# STM32F446RC_single_layer_V2.net
KiCad netlist of a schematic drawn in EAGLE
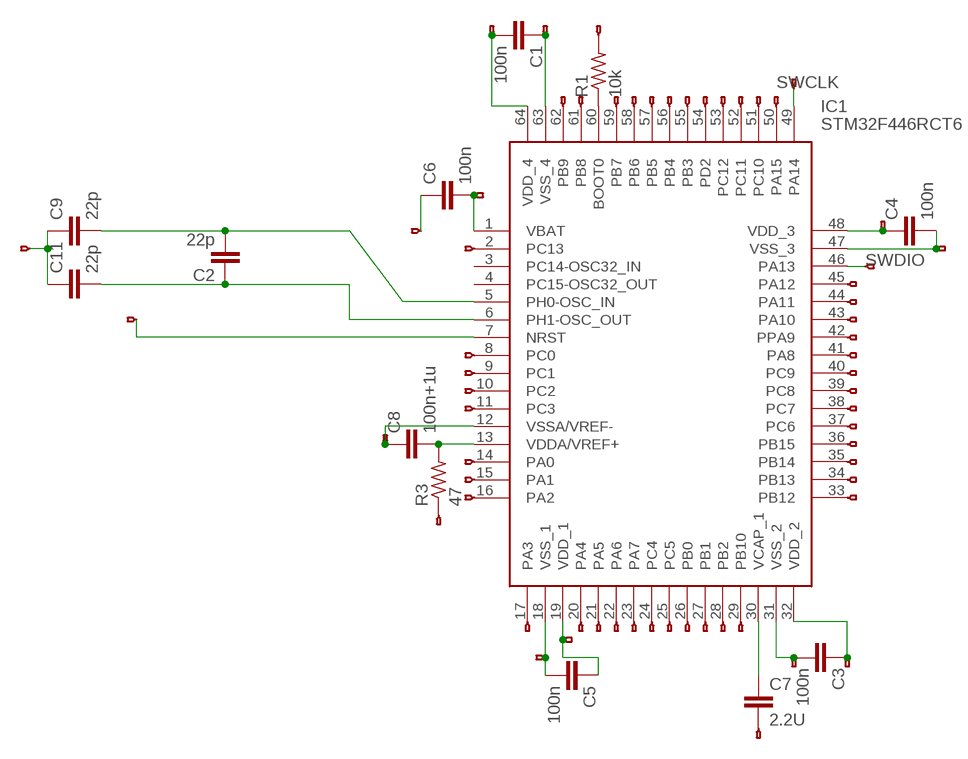
[diagram p0: schematic, sheet 1]

(export (version "E")
  (design (tool "Eeschema 10.0.6"))
  (components
    (comp (ref "C1")
      (value "100n")
      (footprint "eagle-import:C2.5-3")
      (libsource (lib "eagle-import") (part "C2,5-3"))
    )
    (comp (ref "C2")
      (value "22p")
      (footprint "eagle-import:C2.5-3")
      (libsource (lib "eagle-import") (part "C2,5-3"))
    )
    (comp (ref "C3")
      (value "100n")
      (footprint "eagle-import:C2.5-3")
      (libsource (lib "eagle-import") (part "C2,5-3"))
    )
    (comp (ref "C4")
      (value "100n")
      (footprint "eagle-import:C2.5-3")
      (libsource (lib "eagle-import") (part "C2,5-3"))
    )
    (comp (ref "C5")
      (value "100n")
      (footprint "eagle-import:C2.5-3")
      (libsource (lib "eagle-import") (part "C2,5-3"))
    )
    (comp (ref "C6")
      (value "100n")
      (footprint "eagle-import:C2.5-3")
      (libsource (lib "eagle-import") (part "C2,5-3"))
    )
    (comp (ref "C7")
      (value "2.2U")
      (footprint "eagle-import:C2.5-3")
      (libsource (lib "eagle-import") (part "C2,5-3"))
    )
    (comp (ref "C8")
      (value "100n+1u")
      (footprint "eagle-import:C2.5-3")
      (libsource (lib "eagle-import") (part "C2,5-3"))
    )
    (comp (ref "C9")
      (value "22p")
      (footprint "eagle-import:C2.5-3")
      (libsource (lib "eagle-import") (part "C2,5-3"))
    )
    (comp (ref "C11")
      (value "22p")
      (footprint "eagle-import:C2.5-3")
      (libsource (lib "eagle-import") (part "C2,5-3"))
    )
    (comp (ref "IC1")
      (value "STM32F446RCT6")
      (footprint "eagle-import:QFP50P1200X1200X160-64N")
      (fields (field (name "MOUSER_PART_NUMBER") "511-STM32F446RCT6"))
      (libsource (lib "eagle-import") (part "STM32F446RCT6"))
    )
    (comp (ref "JP1")
      (value "HEADERHOLE-HEADERHOLE")
      (footprint "eagle-import:1X1-HEADER-HOLE")
      (libsource (lib "eagle-import") (part "HEADERHOLE-HEADERHOLE"))
    )
    (comp (ref "JP2")
      (value "HEADERHOLE-HEADERHOLE")
      (footprint "eagle-import:1X1-HEADER-HOLE")
      (libsource (lib "eagle-import") (part "HEADERHOLE-HEADERHOLE"))
    )
    (comp (ref "JP3")
      (value "HEADERHOLE-HEADERHOLE")
      (footprint "eagle-import:1X1-HEADER-HOLE")
      (libsource (lib "eagle-import") (part "HEADERHOLE-HEADERHOLE"))
    )
    (comp (ref "JP4")
      (value "HEADERHOLE-HEADERHOLE")
      (footprint "eagle-import:1X1-HEADER-HOLE")
      (libsource (lib "eagle-import") (part "HEADERHOLE-HEADERHOLE"))
    )
    (comp (ref "JP5")
      (value "HEADERHOLE-HEADERHOLE")
      (footprint "eagle-import:1X1-HEADER-HOLE")
      (libsource (lib "eagle-import") (part "HEADERHOLE-HEADERHOLE"))
    )
    (comp (ref "JP6")
      (value "HEADERHOLE-HEADERHOLE")
      (footprint "eagle-import:1X1-HEADER-HOLE")
      (libsource (lib "eagle-import") (part "HEADERHOLE-HEADERHOLE"))
    )
    (comp (ref "JP7")
      (value "HEADERHOLE-HEADERHOLE")
      (footprint "eagle-import:1X1-HEADER-HOLE")
      (libsource (lib "eagle-import") (part "HEADERHOLE-HEADERHOLE"))
    )
    (comp (ref "JP9")
      (value "HEADERHOLE-HEADERHOLE")
      (footprint "eagle-import:1X1-HEADER-HOLE")
      (libsource (lib "eagle-import") (part "HEADERHOLE-HEADERHOLE"))
    )
    (comp (ref "JP10")
      (value "HEADERHOLE-HEADERHOLE")
      (footprint "eagle-import:1X1-HEADER-HOLE")
      (libsource (lib "eagle-import") (part "HEADERHOLE-HEADERHOLE"))
    )
    (comp (ref "JP11")
      (value "HEADERHOLE-HEADERHOLE")
      (footprint "eagle-import:1X1-HEADER-HOLE")
      (libsource (lib "eagle-import") (part "HEADERHOLE-HEADERHOLE"))
    )
    (comp (ref "JP12")
      (value "HEADERHOLE-HEADERHOLE")
      (footprint "eagle-import:1X1-HEADER-HOLE")
      (libsource (lib "eagle-import") (part "HEADERHOLE-HEADERHOLE"))
    )
    (comp (ref "JP13")
      (value "HEADERHOLE-HEADERHOLE")
      (footprint "eagle-import:1X1-HEADER-HOLE")
      (libsource (lib "eagle-import") (part "HEADERHOLE-HEADERHOLE"))
    )
    (comp (ref "JP14")
      (value "HEADERHOLE-HEADERHOLE")
      (footprint "eagle-import:1X1-HEADER-HOLE")
      (libsource (lib "eagle-import") (part "HEADERHOLE-HEADERHOLE"))
    )
    (comp (ref "JP15")
      (value "HEADERHOLE-HEADERHOLE")
      (footprint "eagle-import:1X1-HEADER-HOLE")
      (libsource (lib "eagle-import") (part "HEADERHOLE-HEADERHOLE"))
    )
    (comp (ref "JP16")
      (value "HEADERHOLE-HEADERHOLE")
      (footprint "eagle-import:1X1-HEADER-HOLE")
      (libsource (lib "eagle-import") (part "HEADERHOLE-HEADERHOLE"))
    )
    (comp (ref "JP17")
      (value "HEADERHOLE-HEADERHOLE")
      (footprint "eagle-import:1X1-HEADER-HOLE")
      (libsource (lib "eagle-import") (part "HEADERHOLE-HEADERHOLE"))
    )
    (comp (ref "JP18")
      (value "HEADERHOLE-HEADERHOLE")
      (footprint "eagle-import:1X1-HEADER-HOLE")
      (libsource (lib "eagle-import") (part "HEADERHOLE-HEADERHOLE"))
    )
    (comp (ref "JP19")
      (value "HEADERHOLE-HEADERHOLE")
      (footprint "eagle-import:1X1-HEADER-HOLE")
      (libsource (lib "eagle-import") (part "HEADERHOLE-HEADERHOLE"))
    )
    (comp (ref "JP20")
      (value "HEADERHOLE-HEADERHOLE")
      (footprint "eagle-import:1X1-HEADER-HOLE")
      (libsource (lib "eagle-import") (part "HEADERHOLE-HEADERHOLE"))
    )
    (comp (ref "JP21")
      (value "HEADERHOLE-HEADERHOLE")
      (footprint "eagle-import:1X1-HEADER-HOLE")
      (libsource (lib "eagle-import") (part "HEADERHOLE-HEADERHOLE"))
    )
    (comp (ref "JP22")
      (value "HEADERHOLE-HEADERHOLE")
      (footprint "eagle-import:1X1-HEADER-HOLE")
      (libsource (lib "eagle-import") (part "HEADERHOLE-HEADERHOLE"))
    )
    (comp (ref "JP23")
      (value "HEADERHOLE-HEADERHOLE")
      (footprint "eagle-import:1X1-HEADER-HOLE")
      (libsource (lib "eagle-import") (part "HEADERHOLE-HEADERHOLE"))
    )
    (comp (ref "JP24")
      (value "HEADERHOLE-HEADERHOLE")
      (footprint "eagle-import:1X1-HEADER-HOLE")
      (libsource (lib "eagle-import") (part "HEADERHOLE-HEADERHOLE"))
    )
    (comp (ref "JP25")
      (value "HEADERHOLE-HEADERHOLE")
      (footprint "eagle-import:1X1-HEADER-HOLE")
      (libsource (lib "eagle-import") (part "HEADERHOLE-HEADERHOLE"))
    )
    (comp (ref "JP26")
      (value "HEADERHOLE-HEADERHOLE")
      (footprint "eagle-import:1X1-HEADER-HOLE")
      (libsource (lib "eagle-import") (part "HEADERHOLE-HEADERHOLE"))
    )
    (comp (ref "JP27")
      (value "HEADERHOLE-HEADERHOLE")
      (footprint "eagle-import:1X1-HEADER-HOLE")
      (libsource (lib "eagle-import") (part "HEADERHOLE-HEADERHOLE"))
    )
    (comp (ref "JP28")
      (value "HEADERHOLE-HEADERHOLE")
      (footprint "eagle-import:1X1-HEADER-HOLE")
      (libsource (lib "eagle-import") (part "HEADERHOLE-HEADERHOLE"))
    )
    (comp (ref "JP29")
      (value "HEADERHOLE-HEADERHOLE")
      (footprint "eagle-import:1X1-HEADER-HOLE")
      (libsource (lib "eagle-import") (part "HEADERHOLE-HEADERHOLE"))
    )
    (comp (ref "JP30")
      (value "HEADERHOLE-HEADERHOLE")
      (footprint "eagle-import:1X1-HEADER-HOLE")
      (libsource (lib "eagle-import") (part "HEADERHOLE-HEADERHOLE"))
    )
    (comp (ref "JP31")
      (value "HEADERHOLE-HEADERHOLE")
      (footprint "eagle-import:1X1-HEADER-HOLE")
      (libsource (lib "eagle-import") (part "HEADERHOLE-HEADERHOLE"))
    )
    (comp (ref "JP32")
      (value "HEADERHOLE-HEADERHOLE")
      (footprint "eagle-import:1X1-HEADER-HOLE")
      (libsource (lib "eagle-import") (part "HEADERHOLE-HEADERHOLE"))
    )
    (comp (ref "JP33")
      (value "HEADERHOLE-HEADERHOLE")
      (footprint "eagle-import:1X1-HEADER-HOLE")
      (libsource (lib "eagle-import") (part "HEADERHOLE-HEADERHOLE"))
    )
    (comp (ref "JP34")
      (value "HEADERHOLE-HEADERHOLE")
      (footprint "eagle-import:1X1-HEADER-HOLE")
      (libsource (lib "eagle-import") (part "HEADERHOLE-HEADERHOLE"))
    )
    (comp (ref "JP35")
      (value "HEADERHOLE-HEADERHOLE")
      (footprint "eagle-import:1X1-HEADER-HOLE")
      (libsource (lib "eagle-import") (part "HEADERHOLE-HEADERHOLE"))
    )
    (comp (ref "JP36")
      (value "HEADERHOLE-HEADERHOLE")
      (footprint "eagle-import:1X1-HEADER-HOLE")
      (libsource (lib "eagle-import") (part "HEADERHOLE-HEADERHOLE"))
    )
    (comp (ref "JP37")
      (value "HEADERHOLE-HEADERHOLE")
      (footprint "eagle-import:1X1-HEADER-HOLE")
      (libsource (lib "eagle-import") (part "HEADERHOLE-HEADERHOLE"))
    )
    (comp (ref "JP38")
      (value "HEADERHOLE-HEADERHOLE")
      (footprint "eagle-import:1X1-HEADER-HOLE")
      (libsource (lib "eagle-import") (part "HEADERHOLE-HEADERHOLE"))
    )
    (comp (ref "JP39")
      (value "HEADERHOLE-HEADERHOLE")
      (footprint "eagle-import:1X1-HEADER-HOLE")
      (libsource (lib "eagle-import") (part "HEADERHOLE-HEADERHOLE"))
    )
    (comp (ref "JP40")
      (value "HEADERHOLE-HEADERHOLE")
      (footprint "eagle-import:1X1-HEADER-HOLE")
      (libsource (lib "eagle-import") (part "HEADERHOLE-HEADERHOLE"))
    )
    (comp (ref "JP41")
      (value "HEADERHOLE-HEADERHOLE")
      (footprint "eagle-import:1X1-HEADER-HOLE")
      (libsource (lib "eagle-import") (part "HEADERHOLE-HEADERHOLE"))
    )
    (comp (ref "JP42")
      (value "HEADERHOLE-HEADERHOLE")
      (footprint "eagle-import:1X1-HEADER-HOLE")
      (libsource (lib "eagle-import") (part "HEADERHOLE-HEADERHOLE"))
    )
    (comp (ref "JP43")
      (value "HEADERHOLE-HEADERHOLE")
      (footprint "eagle-import:1X1-HEADER-HOLE")
      (libsource (lib "eagle-import") (part "HEADERHOLE-HEADERHOLE"))
    )
    (comp (ref "JP44")
      (value "HEADERHOLE-HEADERHOLE")
      (footprint "eagle-import:1X1-HEADER-HOLE")
      (libsource (lib "eagle-import") (part "HEADERHOLE-HEADERHOLE"))
    )
    (comp (ref "JP45")
      (value "HEADERHOLE-HEADERHOLE")
      (footprint "eagle-import:1X1-HEADER-HOLE")
      (libsource (lib "eagle-import") (part "HEADERHOLE-HEADERHOLE"))
    )
    (comp (ref "JP46")
      (value "HEADERHOLE-HEADERHOLE")
      (footprint "eagle-import:1X1-HEADER-HOLE")
      (libsource (lib "eagle-import") (part "HEADERHOLE-HEADERHOLE"))
    )
    (comp (ref "JP47")
      (value "HEADERHOLE-HEADERHOLE")
      (footprint "eagle-import:1X1-HEADER-HOLE")
      (libsource (lib "eagle-import") (part "HEADERHOLE-HEADERHOLE"))
    )
    (comp (ref "JP48")
      (value "HEADERHOLE-HEADERHOLE")
      (footprint "eagle-import:1X1-HEADER-HOLE")
      (libsource (lib "eagle-import") (part "HEADERHOLE-HEADERHOLE"))
    )
    (comp (ref "JP49")
      (value "HEADERHOLE-HEADERHOLE")
      (footprint "eagle-import:1X1-HEADER-HOLE")
      (libsource (lib "eagle-import") (part "HEADERHOLE-HEADERHOLE"))
    )
    (comp (ref "JP50")
      (value "HEADERHOLE-HEADERHOLE")
      (footprint "eagle-import:1X1-HEADER-HOLE")
      (libsource (lib "eagle-import") (part "HEADERHOLE-HEADERHOLE"))
    )
    (comp (ref "JP51")
      (value "HEADERHOLE-HEADERHOLE")
      (footprint "eagle-import:1X1-HEADER-HOLE")
      (libsource (lib "eagle-import") (part "HEADERHOLE-HEADERHOLE"))
    )
    (comp (ref "JP52")
      (value "HEADERHOLE-HEADERHOLE")
      (footprint "eagle-import:1X1-HEADER-HOLE")
      (libsource (lib "eagle-import") (part "HEADERHOLE-HEADERHOLE"))
    )
    (comp (ref "JP53")
      (value "HEADERHOLE-HEADERHOLE")
      (footprint "eagle-import:1X1-HEADER-HOLE")
      (libsource (lib "eagle-import") (part "HEADERHOLE-HEADERHOLE"))
    )
    (comp (ref "JP54")
      (value "HEADERHOLE-HEADERHOLE")
      (footprint "eagle-import:1X1-HEADER-HOLE")
      (libsource (lib "eagle-import") (part "HEADERHOLE-HEADERHOLE"))
    )
    (comp (ref "JP55")
      (value "HEADERHOLE-HEADERHOLE")
      (footprint "eagle-import:1X1-HEADER-HOLE")
      (libsource (lib "eagle-import") (part "HEADERHOLE-HEADERHOLE"))
    )
    (comp (ref "JP56")
      (value "HEADERHOLE-HEADERHOLE")
      (footprint "eagle-import:1X1-HEADER-HOLE")
      (libsource (lib "eagle-import") (part "HEADERHOLE-HEADERHOLE"))
    )
    (comp (ref "JP57")
      (value "HEADERHOLE-HEADERHOLE")
      (footprint "eagle-import:1X1-HEADER-HOLE")
      (libsource (lib "eagle-import") (part "HEADERHOLE-HEADERHOLE"))
    )
    (comp (ref "JP58")
      (value "HEADERHOLE-HEADERHOLE")
      (footprint "eagle-import:1X1-HEADER-HOLE")
      (libsource (lib "eagle-import") (part "HEADERHOLE-HEADERHOLE"))
    )
    (comp (ref "JP59")
      (value "HEADERHOLE-HEADERHOLE")
      (footprint "eagle-import:1X1-HEADER-HOLE")
      (libsource (lib "eagle-import") (part "HEADERHOLE-HEADERHOLE"))
    )
    (comp (ref "JP61")
      (value "HEADERHOLE-HEADERHOLE")
      (footprint "eagle-import:1X1-HEADER-HOLE")
      (libsource (lib "eagle-import") (part "HEADERHOLE-HEADERHOLE"))
    )
    (comp (ref "JP62")
      (value "HEADERHOLE-HEADERHOLE")
      (footprint "eagle-import:1X1-HEADER-HOLE")
      (libsource (lib "eagle-import") (part "HEADERHOLE-HEADERHOLE"))
    )
    (comp (ref "JP63")
      (value "HEADERHOLE-HEADERHOLE")
      (footprint "eagle-import:1X1-HEADER-HOLE")
      (libsource (lib "eagle-import") (part "HEADERHOLE-HEADERHOLE"))
    )
    (comp (ref "JP65")
      (value "HEADERHOLE-HEADERHOLE")
      (footprint "eagle-import:1X1-HEADER-HOLE")
      (libsource (lib "eagle-import") (part "HEADERHOLE-HEADERHOLE"))
    )
    (comp (ref "R1")
      (value "10k")
      (footprint "eagle-import:0204V")
      (libsource (lib "eagle-import") (part "R-US_0204/2V"))
    )
    (comp (ref "R3")
      (value "47")
      (footprint "eagle-import:0204V")
      (libsource (lib "eagle-import") (part "R-US_0204/2V"))
    )
  )
  (nets
    (net (code "1") (name "/SWCLK") (class "Default")
      (node (ref "IC1") (pin "49") (pinfunction "PA14_49") (pintype "bidirectional"))
      (node (ref "JP55") (pin "1") (pinfunction "P$1_1") (pintype "bidirectional"))
    )
    (net (code "2") (name "/SWDIO") (class "Default")
      (node (ref "IC1") (pin "46") (pinfunction "PA13_46") (pintype "bidirectional"))
      (node (ref "JP54") (pin "1") (pinfunction "P$1_1") (pintype "bidirectional"))
    )
    (net (code "3") (name "Net-(IC1-BOOT0)") (class "Default")
      (node (ref "IC1") (pin "60") (pinfunction "BOOT0_60") (pintype "bidirectional"))
      (node (ref "R1") (pin "1") (pinfunction "1_1") (pintype "passive"))
    )
    (net (code "4") (name "Net-(IC1-NRST)") (class "Default")
      (node (ref "IC1") (pin "7") (pinfunction "NRST_7") (pintype "bidirectional"))
      (node (ref "JP63") (pin "1") (pinfunction "P$1_1") (pintype "bidirectional"))
    )
    (net (code "5") (name "Net-(IC1-PA0)") (class "Default")
      (node (ref "IC1") (pin "14") (pinfunction "PA0_14") (pintype "bidirectional"))
      (node (ref "JP34") (pin "1") (pinfunction "P$1_1") (pintype "bidirectional"))
    )
    (net (code "6") (name "Net-(IC1-PA1)") (class "Default")
      (node (ref "IC1") (pin "15") (pinfunction "PA1_15") (pintype "bidirectional"))
      (node (ref "JP35") (pin "1") (pinfunction "P$1_1") (pintype "bidirectional"))
    )
    (net (code "7") (name "Net-(IC1-PA2)") (class "Default")
      (node (ref "IC1") (pin "16") (pinfunction "PA2_16") (pintype "bidirectional"))
      (node (ref "JP36") (pin "1") (pinfunction "P$1_1") (pintype "bidirectional"))
    )
    (net (code "8") (name "Net-(IC1-PA3)") (class "Default")
      (node (ref "IC1") (pin "17") (pinfunction "PA3_17") (pintype "bidirectional"))
      (node (ref "JP24") (pin "1") (pinfunction "P$1_1") (pintype "bidirectional"))
    )
    (net (code "9") (name "Net-(IC1-PA4)") (class "Default")
      (node (ref "IC1") (pin "20") (pinfunction "PA4_20") (pintype "bidirectional"))
      (node (ref "JP21") (pin "1") (pinfunction "P$1_1") (pintype "bidirectional"))
    )
    (net (code "10") (name "Net-(IC1-PA5)") (class "Default")
      (node (ref "IC1") (pin "21") (pinfunction "PA5_21") (pintype "bidirectional"))
      (node (ref "JP19") (pin "1") (pinfunction "P$1_1") (pintype "bidirectional"))
    )
    (net (code "11") (name "Net-(IC1-PA6)") (class "Default")
      (node (ref "IC1") (pin "22") (pinfunction "PA6_22") (pintype "bidirectional"))
      (node (ref "JP9") (pin "1") (pinfunction "P$1_1") (pintype "bidirectional"))
    )
    (net (code "12") (name "Net-(IC1-PA7)") (class "Default")
      (node (ref "IC1") (pin "23") (pinfunction "PA7_23") (pintype "bidirectional"))
      (node (ref "JP11") (pin "1") (pinfunction "P$1_1") (pintype "bidirectional"))
    )
    (net (code "13") (name "Net-(IC1-PA8)") (class "Default")
      (node (ref "IC1") (pin "41") (pinfunction "PA8_41") (pintype "bidirectional"))
      (node (ref "JP28") (pin "1") (pinfunction "P$1_1") (pintype "bidirectional"))
    )
    (net (code "14") (name "Net-(IC1-PA10)") (class "Default")
      (node (ref "IC1") (pin "43") (pinfunction "PA10_43") (pintype "bidirectional"))
      (node (ref "JP33") (pin "1") (pinfunction "P$1_1") (pintype "bidirectional"))
    )
    (net (code "15") (name "Net-(IC1-PA11)") (class "Default")
      (node (ref "IC1") (pin "44") (pinfunction "PA11_44") (pintype "bidirectional"))
      (node (ref "JP32") (pin "1") (pinfunction "P$1_1") (pintype "bidirectional"))
    )
    (net (code "16") (name "Net-(IC1-PA12)") (class "Default")
      (node (ref "IC1") (pin "45") (pinfunction "PA12_45") (pintype "bidirectional"))
      (node (ref "JP25") (pin "1") (pinfunction "P$1_1") (pintype "bidirectional"))
    )
    (net (code "17") (name "Net-(IC1-PA15)") (class "Default")
      (node (ref "IC1") (pin "50") (pinfunction "PA15_50") (pintype "bidirectional"))
      (node (ref "JP45") (pin "1") (pinfunction "P$1_1") (pintype "bidirectional"))
    )
    (net (code "18") (name "Net-(IC1-PB0)") (class "Default")
      (node (ref "IC1") (pin "26") (pinfunction "PB0_26") (pintype "bidirectional"))
      (node (ref "JP22") (pin "1") (pinfunction "P$1_1") (pintype "bidirectional"))
    )
    (net (code "19") (name "Net-(IC1-PB1)") (class "Default")
      (node (ref "IC1") (pin "27") (pinfunction "PB1_27") (pintype "bidirectional"))
      (node (ref "JP17") (pin "1") (pinfunction "P$1_1") (pintype "bidirectional"))
    )
    (net (code "20") (name "Net-(IC1-PB2)") (class "Default")
      (node (ref "IC1") (pin "28") (pinfunction "PB2_28") (pintype "bidirectional"))
      (node (ref "JP16") (pin "1") (pinfunction "P$1_1") (pintype "bidirectional"))
    )
    (net (code "21") (name "Net-(IC1-PB3)") (class "Default")
      (node (ref "IC1") (pin "55") (pinfunction "PB3_55") (pintype "bidirectional"))
      (node (ref "JP44") (pin "1") (pinfunction "P$1_1") (pintype "bidirectional"))
    )
    (net (code "22") (name "Net-(IC1-PB4)") (class "Default")
      (node (ref "IC1") (pin "56") (pinfunction "PB4_56") (pintype "bidirectional"))
      (node (ref "JP40") (pin "1") (pinfunction "P$1_1") (pintype "bidirectional"))
    )
    (net (code "23") (name "Net-(IC1-PB5)") (class "Default")
      (node (ref "IC1") (pin "57") (pinfunction "PB5_57") (pintype "bidirectional"))
      (node (ref "JP41") (pin "1") (pinfunction "P$1_1") (pintype "bidirectional"))
    )
    (net (code "24") (name "Net-(IC1-PB6)") (class "Default")
      (node (ref "IC1") (pin "58") (pinfunction "PB6_58") (pintype "bidirectional"))
      (node (ref "JP42") (pin "1") (pinfunction "P$1_1") (pintype "bidirectional"))
    )
    (net (code "25") (name "Net-(IC1-PB7)") (class "Default")
      (node (ref "IC1") (pin "59") (pinfunction "PB7_59") (pintype "bidirectional"))
      (node (ref "JP43") (pin "1") (pinfunction "P$1_1") (pintype "bidirectional"))
    )
    (net (code "26") (name "Net-(IC1-PB8)") (class "Default")
      (node (ref "IC1") (pin "61") (pinfunction "PB8_61") (pintype "bidirectional"))
      (node (ref "JP46") (pin "1") (pinfunction "P$1_1") (pintype "bidirectional"))
    )
    (net (code "27") (name "Net-(IC1-PB9)") (class "Default")
      (node (ref "IC1") (pin "62") (pinfunction "PB9_62") (pintype "bidirectional"))
      (node (ref "JP47") (pin "1") (pinfunction "P$1_1") (pintype "bidirectional"))
    )
    (net (code "28") (name "Net-(IC1-PB10)") (class "Default")
      (node (ref "IC1") (pin "29") (pinfunction "PB10_29") (pintype "bidirectional"))
      (node (ref "JP14") (pin "1") (pinfunction "P$1_1") (pintype "bidirectional"))
    )
    (net (code "29") (name "Net-(IC1-PB12)") (class "Default")
      (node (ref "IC1") (pin "33") (pinfunction "PB12_33") (pintype "bidirectional"))
      (node (ref "JP18") (pin "1") (pinfunction "P$1_1") (pintype "bidirectional"))
    )
    (net (code "30") (name "Net-(IC1-PB13)") (class "Default")
      (node (ref "IC1") (pin "34") (pinfunction "PB13_34") (pintype "bidirectional"))
      (node (ref "JP13") (pin "1") (pinfunction "P$1_1") (pintype "bidirectional"))
    )
    (net (code "31") (name "Net-(IC1-PB14)") (class "Default")
      (node (ref "IC1") (pin "35") (pinfunction "PB14_35") (pintype "bidirectional"))
      (node (ref "JP6") (pin "1") (pinfunction "P$1_1") (pintype "bidirectional"))
    )
    (net (code "32") (name "Net-(IC1-PB15)") (class "Default")
      (node (ref "IC1") (pin "36") (pinfunction "PB15_36") (pintype "bidirectional"))
      (node (ref "JP10") (pin "1") (pinfunction "P$1_1") (pintype "bidirectional"))
    )
    (net (code "33") (name "Net-(IC1-PC0)") (class "Default")
      (node (ref "IC1") (pin "8") (pinfunction "PC0_8") (pintype "bidirectional"))
      (node (ref "JP29") (pin "1") (pinfunction "P$1_1") (pintype "bidirectional"))
    )
    (net (code "34") (name "Net-(IC1-PC1)") (class "Default")
      (node (ref "IC1") (pin "9") (pinfunction "PC1_9") (pintype "bidirectional"))
      (node (ref "JP27") (pin "1") (pinfunction "P$1_1") (pintype "bidirectional"))
    )
    (net (code "35") (name "Net-(IC1-PC2)") (class "Default")
      (node (ref "IC1") (pin "10") (pinfunction "PC2_10") (pintype "bidirectional"))
      (node (ref "JP3") (pin "1") (pinfunction "P$1_1") (pintype "bidirectional"))
    )
    (net (code "36") (name "Net-(IC1-PC3)") (class "Default")
      (node (ref "IC1") (pin "11") (pinfunction "PC3_11") (pintype "bidirectional"))
      (node (ref "JP4") (pin "1") (pinfunction "P$1_1") (pintype "bidirectional"))
    )
    (net (code "37") (name "Net-(IC1-PC4)") (class "Default")
      (node (ref "IC1") (pin "24") (pinfunction "PC4_24") (pintype "bidirectional"))
      (node (ref "JP12") (pin "1") (pinfunction "P$1_1") (pintype "bidirectional"))
    )
    (net (code "38") (name "Net-(IC1-PC5)") (class "Default")
      (node (ref "IC1") (pin "25") (pinfunction "PC5_25") (pintype "bidirectional"))
      (node (ref "JP23") (pin "1") (pinfunction "P$1_1") (pintype "bidirectional"))
    )
    (net (code "39") (name "Net-(IC1-PC6)") (class "Default")
      (node (ref "IC1") (pin "37") (pinfunction "PC6_37") (pintype "bidirectional"))
      (node (ref "JP1") (pin "1") (pinfunction "P$1_1") (pintype "bidirectional"))
    )
    (net (code "40") (name "Net-(IC1-PC7)") (class "Default")
      (node (ref "IC1") (pin "38") (pinfunction "PC7_38") (pintype "bidirectional"))
      (node (ref "JP15") (pin "1") (pinfunction "P$1_1") (pintype "bidirectional"))
    )
    (net (code "41") (name "Net-(IC1-PC8)") (class "Default")
      (node (ref "IC1") (pin "39") (pinfunction "PC8_39") (pintype "bidirectional"))
      (node (ref "JP2") (pin "1") (pinfunction "P$1_1") (pintype "bidirectional"))
    )
    (net (code "42") (name "Net-(IC1-PC9)") (class "Default")
      (node (ref "IC1") (pin "40") (pinfunction "PC9_40") (pintype "bidirectional"))
      (node (ref "JP30") (pin "1") (pinfunction "P$1_1") (pintype "bidirectional"))
    )
    (net (code "43") (name "Net-(IC1-PC10)") (class "Default")
      (node (ref "IC1") (pin "51") (pinfunction "PC10_51") (pintype "bidirectional"))
      (node (ref "JP37") (pin "1") (pinfunction "P$1_1") (pintype "bidirectional"))
    )
    (net (code "44") (name "Net-(IC1-PC11)") (class "Default")
      (node (ref "IC1") (pin "52") (pinfunction "PC11_52") (pintype "bidirectional"))
      (node (ref "JP5") (pin "1") (pinfunction "P$1_1") (pintype "bidirectional"))
    )
    (net (code "45") (name "Net-(IC1-PC12)") (class "Default")
      (node (ref "IC1") (pin "53") (pinfunction "PC12_53") (pintype "bidirectional"))
      (node (ref "JP39") (pin "1") (pinfunction "P$1_1") (pintype "bidirectional"))
    )
    (net (code "46") (name "Net-(IC1-PC13)") (class "Default")
      (node (ref "IC1") (pin "2") (pinfunction "PC13_2") (pintype "bidirectional"))
      (node (ref "JP26") (pin "1") (pinfunction "P$1_1") (pintype "bidirectional"))
    )
    (net (code "47") (name "Net-(IC1-PD2)") (class "Default")
      (node (ref "IC1") (pin "54") (pinfunction "PD2_54") (pintype "bidirectional"))
      (node (ref "JP38") (pin "1") (pinfunction "P$1_1") (pintype "bidirectional"))
    )
    (net (code "48") (name "Net-(IC1-PH0-OSC_IN)") (class "Default")
      (node (ref "C2") (pin "2") (pinfunction "2_2") (pintype "passive"))
      (node (ref "C9") (pin "2") (pinfunction "2_2") (pintype "passive"))
      (node (ref "IC1") (pin "5") (pinfunction "PH0-OSC_IN_5") (pintype "bidirectional"))
    )
    (net (code "49") (name "Net-(IC1-PH1-OSC_OUT)") (class "Default")
      (node (ref "C11") (pin "2") (pinfunction "2_2") (pintype "passive"))
      (node (ref "C2") (pin "1") (pinfunction "1_1") (pintype "passive"))
      (node (ref "IC1") (pin "6") (pinfunction "PH1-OSC_OUT_6") (pintype "bidirectional"))
    )
    (net (code "50") (name "Net-(IC1-PPA9)") (class "Default")
      (node (ref "IC1") (pin "42") (pinfunction "PPA9_42") (pintype "bidirectional"))
      (node (ref "JP31") (pin "1") (pinfunction "P$1_1") (pintype "bidirectional"))
    )
    (net (code "51") (name "Net-(IC1-VBAT)") (class "Default")
      (node (ref "C6") (pin "2") (pinfunction "2_2") (pintype "passive"))
      (node (ref "IC1") (pin "1") (pinfunction "VBAT_1") (pintype "bidirectional"))
      (node (ref "JP7") (pin "1") (pinfunction "P$1_1") (pintype "bidirectional"))
    )
    (net (code "52") (name "Net-(IC1-VCAP_1)") (class "Default")
      (node (ref "C7") (pin "1") (pinfunction "1_1") (pintype "passive"))
      (node (ref "IC1") (pin "30") (pinfunction "VCAP_1_30") (pintype "bidirectional"))
    )
    (net (code "53") (name "Net-(IC1-VDDA{slash}VREF+)") (class "Default")
      (node (ref "C8") (pin "2") (pinfunction "2_2") (pintype "passive"))
      (node (ref "IC1") (pin "13") (pinfunction "VDDA/VREF+_13") (pintype "bidirectional"))
      (node (ref "R3") (pin "2") (pinfunction "2_2") (pintype "passive"))
    )
    (net (code "54") (name "Net-(IC1-VDD_1)") (class "Default")
      (node (ref "C5") (pin "1") (pinfunction "1_1") (pintype "passive"))
      (node (ref "IC1") (pin "19") (pinfunction "VDD_1_19") (pintype "bidirectional"))
      (node (ref "JP48") (pin "1") (pinfunction "P$1_1") (pintype "bidirectional"))
    )
    (net (code "55") (name "Net-(IC1-VDD_2)") (class "Default")
      (node (ref "C3") (pin "1") (pinfunction "1_1") (pintype "passive"))
      (node (ref "IC1") (pin "32") (pinfunction "VDD_2_32") (pintype "bidirectional"))
      (node (ref "JP51") (pin "1") (pinfunction "P$1_1") (pintype "bidirectional"))
    )
    (net (code "56") (name "Net-(IC1-VDD_3)") (class "Default")
      (node (ref "C4") (pin "1") (pinfunction "1_1") (pintype "passive"))
      (node (ref "IC1") (pin "48") (pinfunction "VDD_3_48") (pintype "bidirectional"))
      (node (ref "JP53") (pin "1") (pinfunction "P$1_1") (pintype "bidirectional"))
    )
    (net (code "57") (name "Net-(IC1-VDD_4)") (class "Default")
      (node (ref "C1") (pin "2") (pinfunction "2_2") (pintype "passive"))
      (node (ref "IC1") (pin "64") (pinfunction "VDD_4_64") (pintype "bidirectional"))
      (node (ref "JP58") (pin "1") (pinfunction "P$1_1") (pintype "bidirectional"))
    )
    (net (code "58") (name "Net-(IC1-VSSA{slash}VREF-)") (class "Default")
      (node (ref "C8") (pin "1") (pinfunction "1_1") (pintype "passive"))
      (node (ref "IC1") (pin "12") (pinfunction "VSSA/VREF-_12") (pintype "bidirectional"))
      (node (ref "JP62") (pin "1") (pinfunction "P$1_1") (pintype "bidirectional"))
    )
    (net (code "59") (name "Net-(IC1-VSS_1)") (class "Default")
      (node (ref "C5") (pin "2") (pinfunction "2_2") (pintype "passive"))
      (node (ref "IC1") (pin "18") (pinfunction "VSS_1_18") (pintype "bidirectional"))
      (node (ref "JP20") (pin "1") (pinfunction "P$1_1") (pintype "bidirectional"))
    )
    (net (code "60") (name "Net-(IC1-VSS_2)") (class "Default")
      (node (ref "C3") (pin "2") (pinfunction "2_2") (pintype "passive"))
      (node (ref "IC1") (pin "31") (pinfunction "VSS_2_31") (pintype "bidirectional"))
      (node (ref "JP50") (pin "1") (pinfunction "P$1_1") (pintype "bidirectional"))
    )
    (net (code "61") (name "Net-(IC1-VSS_3)") (class "Default")
      (node (ref "C4") (pin "2") (pinfunction "2_2") (pintype "passive"))
      (node (ref "IC1") (pin "47") (pinfunction "VSS_3_47") (pintype "bidirectional"))
      (node (ref "JP52") (pin "1") (pinfunction "P$1_1") (pintype "bidirectional"))
    )
    (net (code "62") (name "Net-(IC1-VSS_4)") (class "Default")
      (node (ref "C1") (pin "1") (pinfunction "1_1") (pintype "passive"))
      (node (ref "IC1") (pin "63") (pinfunction "VSS_4_63") (pintype "bidirectional"))
      (node (ref "JP57") (pin "1") (pinfunction "P$1_1") (pintype "bidirectional"))
    )
    (net (code "63") (name "Net-(JP49-P$1)") (class "Default")
      (node (ref "C7") (pin "2") (pinfunction "2_2") (pintype "passive"))
      (node (ref "JP49") (pin "1") (pinfunction "P$1_1") (pintype "bidirectional"))
    )
    (net (code "64") (name "Net-(JP56-P$1)") (class "Default")
      (node (ref "JP56") (pin "1") (pinfunction "P$1_1") (pintype "bidirectional"))
      (node (ref "R1") (pin "2") (pinfunction "2_2") (pintype "passive"))
    )
    (net (code "65") (name "Net-(JP59-P$1)") (class "Default")
      (node (ref "C6") (pin "1") (pinfunction "1_1") (pintype "passive"))
      (node (ref "JP59") (pin "1") (pinfunction "P$1_1") (pintype "bidirectional"))
    )
    (net (code "66") (name "Net-(JP61-P$1)") (class "Default")
      (node (ref "JP61") (pin "1") (pinfunction "P$1_1") (pintype "bidirectional"))
      (node (ref "R3") (pin "1") (pinfunction "1_1") (pintype "passive"))
    )
    (net (code "67") (name "Net-(JP65-P$1)") (class "Default")
      (node (ref "C11") (pin "1") (pinfunction "1_1") (pintype "passive"))
      (node (ref "C9") (pin "1") (pinfunction "1_1") (pintype "passive"))
      (node (ref "JP65") (pin "1") (pinfunction "P$1_1") (pintype "bidirectional"))
    )
    (net (code "68") (name "unconnected-(IC1-PC14-OSC32_IN-Pad3)") (class "Default")
      (node (ref "IC1") (pin "3") (pinfunction "PC14-OSC32_IN_3") (pintype "bidirectional"))
    )
    (net (code "69") (name "unconnected-(IC1-PC15-OSC32_OUT-Pad4)") (class "Default")
      (node (ref "IC1") (pin "4") (pinfunction "PC15-OSC32_OUT_4") (pintype "bidirectional"))
    )
  )
)
